# ACS723_Low_Current_Sensor_v01.net
KiCad netlist of a schematic drawn in EAGLE
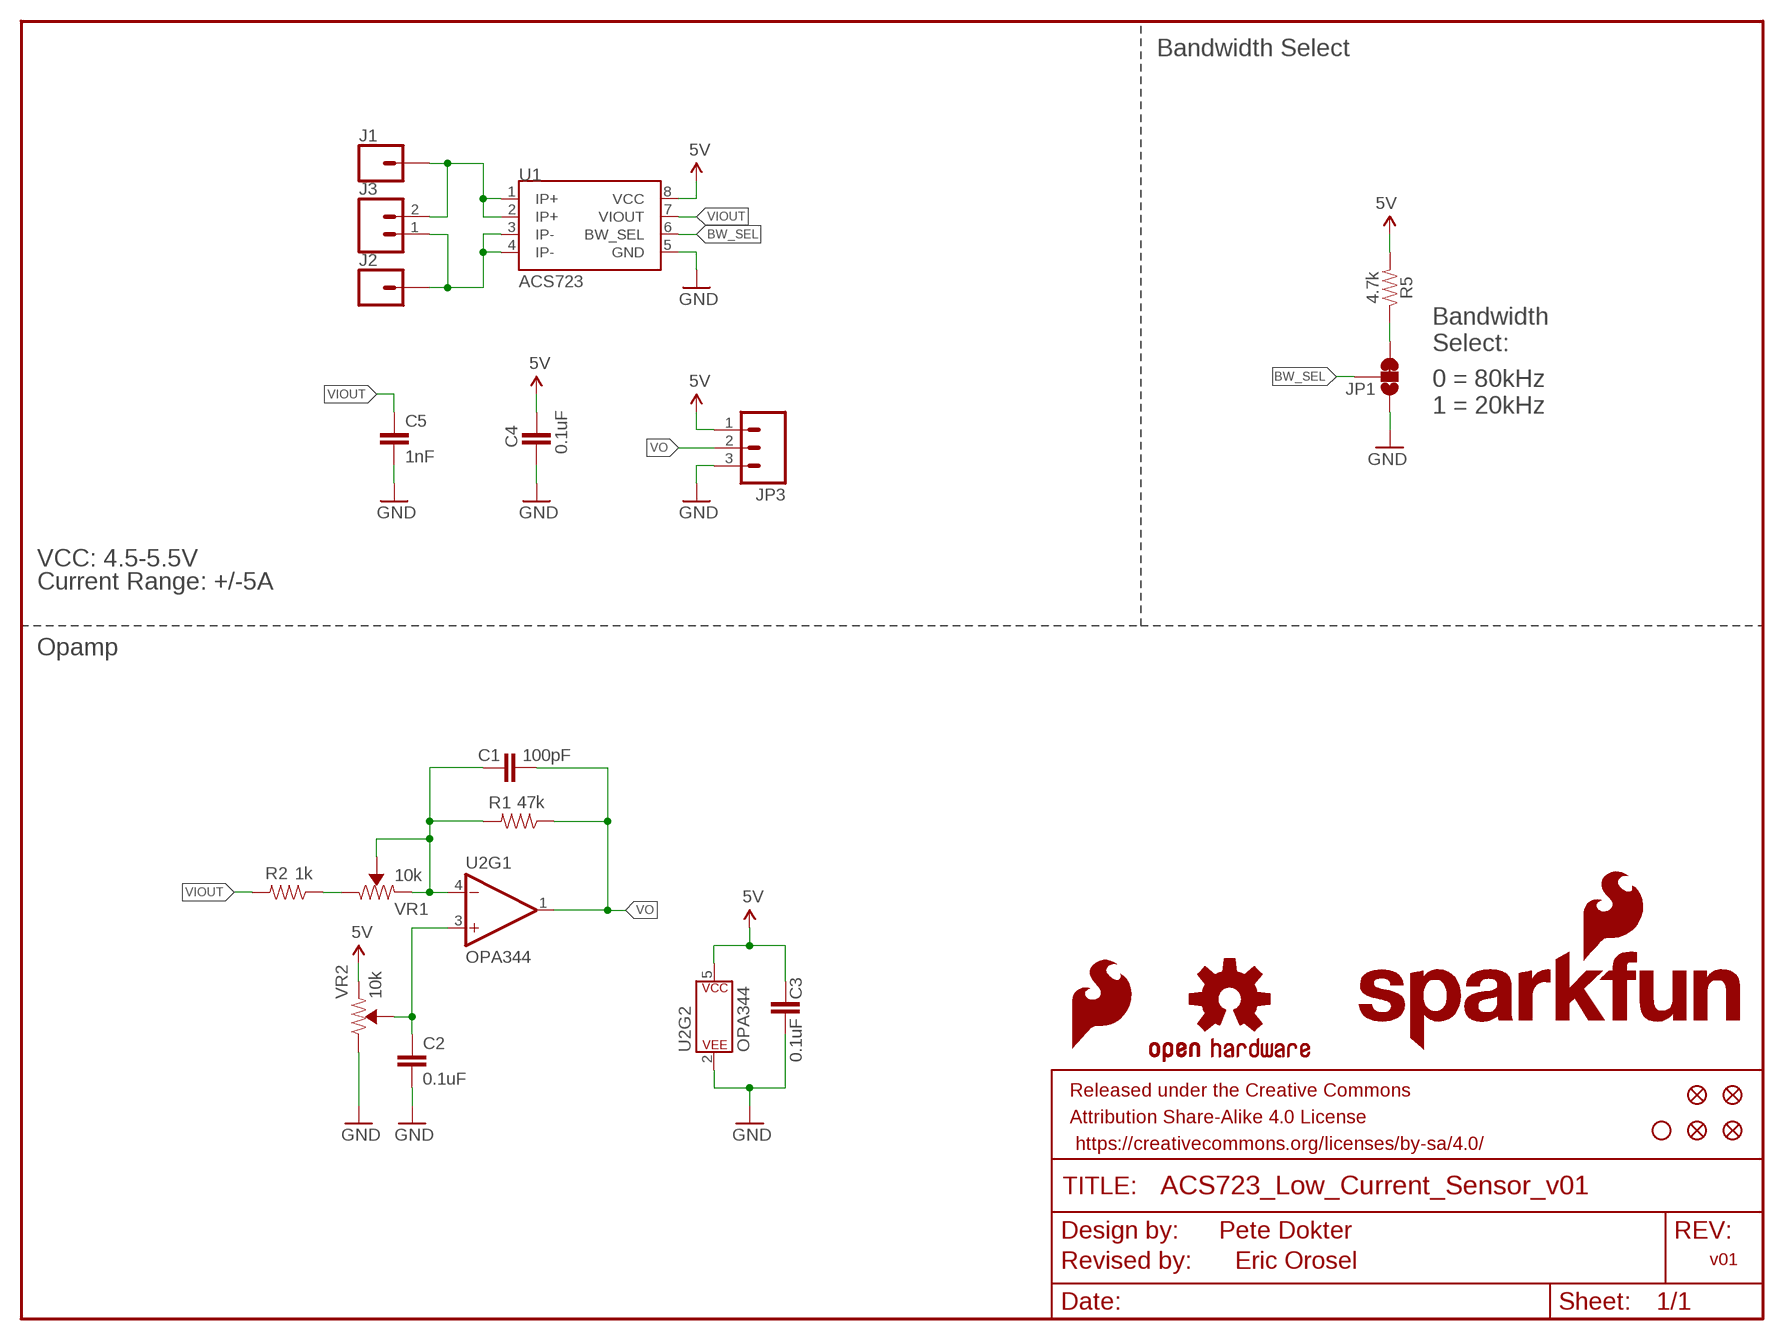
[diagram p0: schematic, sheet 1]

(export (version "E")
  (design (tool "Eeschema 10.0.6"))
  (components
    (comp (ref "C1")
      (value "100pF")
      (footprint "eagle-import:0603")
      (libsource (lib "eagle-import") (part "100PF-0603-50V-5%"))
    )
    (comp (ref "C2")
      (value "0.1uF")
      (footprint "eagle-import:0603")
      (libsource (lib "eagle-import") (part "0.1UF-0603-25V-(+80/-20%)"))
    )
    (comp (ref "C3")
      (value "0.1uF")
      (footprint "eagle-import:0603")
      (libsource (lib "eagle-import") (part "0.1UF-0603-25V-(+80/-20%)"))
    )
    (comp (ref "C4")
      (value "0.1uF")
      (footprint "eagle-import:0603")
      (libsource (lib "eagle-import") (part "0.1UF-0603-25V-(+80/-20%)"))
    )
    (comp (ref "C5")
      (value "1nF")
      (footprint "eagle-import:0603")
      (libsource (lib "eagle-import") (part "1.0NF/1000PF-0603-50V-10%"))
    )
    (comp (ref "FD1")
      (value "FIDUCIAL1X2")
      (footprint "eagle-import:FIDUCIAL-1X2")
      (libsource (lib "eagle-import") (part "FIDUCIAL1X2"))
    )
    (comp (ref "FD2")
      (value "FIDUCIAL1X2")
      (footprint "eagle-import:FIDUCIAL-1X2")
      (libsource (lib "eagle-import") (part "FIDUCIAL1X2"))
    )
    (comp (ref "FD3")
      (value "FIDUCIAL1X2")
      (footprint "eagle-import:FIDUCIAL-1X2")
      (libsource (lib "eagle-import") (part "FIDUCIAL1X2"))
    )
    (comp (ref "FD4")
      (value "FIDUCIAL1X2")
      (footprint "eagle-import:FIDUCIAL-1X2")
      (libsource (lib "eagle-import") (part "FIDUCIAL1X2"))
    )
    (comp (ref "FRAME1")
      (value "FRAME-LETTER")
      (footprint "eagle-import:CREATIVE_COMMONS")
      (libsource (lib "eagle-import") (part "FRAME-LETTER"))
    )
    (comp (ref "H1")
      (value "STAND-OFFTIGHT")
      (footprint "eagle-import:STAND-OFF-TIGHT")
      (libsource (lib "eagle-import") (part "STAND-OFFTIGHT"))
    )
    (comp (ref "J1")
      (value "CONN_01SMTSO-256-ET-0.165DIA")
      (footprint "eagle-import:SMTSO-256-ET-0.165DIA")
      (libsource (lib "eagle-import") (part "CONN_01SMTSO-256-ET-0.165DIA"))
    )
    (comp (ref "J2")
      (value "CONN_01SMTSO-256-ET-0.165DIA")
      (footprint "eagle-import:SMTSO-256-ET-0.165DIA")
      (libsource (lib "eagle-import") (part "CONN_01SMTSO-256-ET-0.165DIA"))
    )
    (comp (ref "J3")
      (value "CONN_021X02_NO_SILK")
      (footprint "eagle-import:1X02_NO_SILK")
      (libsource (lib "eagle-import") (part "CONN_021X02_NO_SILK"))
    )
    (comp (ref "JP1")
      (value "JUMPER-SMT_3_1-NC_TRACE_SILK")
      (footprint "eagle-import:SMT-JUMPER_3_1-NC_TRACE_SILK")
      (libsource (lib "eagle-import") (part "JUMPER-SMT_3_1-NC_TRACE_SILK"))
    )
    (comp (ref "JP3")
      (value "M03PTH")
      (footprint "eagle-import:1X03")
      (libsource (lib "eagle-import") (part "M03PTH"))
    )
    (comp (ref "LOGO1")
      (value "SFE_LOGO_NAME_FLAME.1_INCH")
      (footprint "eagle-import:SFE_LOGO_NAME_FLAME_.1")
      (libsource (lib "eagle-import") (part "SFE_LOGO_NAME_FLAME.1_INCH"))
    )
    (comp (ref "LOGO2")
      (value "OSHW-LOGOS")
      (footprint "eagle-import:OSHW-LOGO-S")
      (libsource (lib "eagle-import") (part "OSHW-LOGOS"))
    )
    (comp (ref "LOGO3")
      (value "SFE_LOGO_FLAME.1_INCH")
      (footprint "eagle-import:SFE_LOGO_FLAME_.1")
      (libsource (lib "eagle-import") (part "SFE_LOGO_FLAME.1_INCH"))
    )
    (comp (ref "R1")
      (value "47k")
      (footprint "eagle-import:0603")
      (libsource (lib "eagle-import") (part "47KOHM-0603-1/10W-1%"))
    )
    (comp (ref "R2")
      (value "1k")
      (footprint "eagle-import:0603")
      (libsource (lib "eagle-import") (part "1KOHM-0603-1/10W-1%"))
    )
    (comp (ref "R5")
      (value "4.7k")
      (footprint "eagle-import:0603")
      (libsource (lib "eagle-import") (part "4.7KOHM-0603-1/10W-1%"))
    )
    (comp (ref "U1")
      (value "ACS723")
      (footprint "eagle-import:SO08")
      (fields (field (name "PART_#") "ACS723ACS723LLCTR-05AB-T2"))
      (libsource (lib "eagle-import") (part "ACS723"))
    )
    (comp (ref "U2")
      (value "OPA344")
      (footprint "eagle-import:SOT23-5")
      (libsource (lib "eagle-import") (part "OPA344"))
    )
    (comp (ref "VR1")
      (value "10k")
      (footprint "eagle-import:TRIMPOT-SMD-TC33X")
      (libsource (lib "eagle-import") (part "TRIMPOT-SMD-3MM-OPEN-1/10W-25%"))
    )
    (comp (ref "VR2")
      (value "10k")
      (footprint "eagle-import:TRIMPOT-SMD-TC33X")
      (libsource (lib "eagle-import") (part "TRIMPOT-SMD-3MM-OPEN-1/10W-25%"))
    )
  )
  (nets
    (net (code "1") (name "5V") (class "Default")
      (node (ref "C3") (pin "1") (pinfunction "1_1") (pintype "passive"))
      (node (ref "C4") (pin "2") (pinfunction "2_2") (pintype "passive"))
      (node (ref "JP3") (pin "1") (pinfunction "1_1") (pintype "passive"))
      (node (ref "R5") (pin "2") (pinfunction "2_2") (pintype "passive"))
      (node (ref "U1") (pin "8") (pinfunction "VCC_8") (pintype "bidirectional"))
      (node (ref "U2") (pin "5") (pinfunction "P$V+_5") (pintype "bidirectional"))
      (node (ref "VR2") (pin "3") (pinfunction "CCW_3") (pintype "passive"))
    )
    (net (code "2") (name "BW_SEL") (class "Default")
      (node (ref "JP1") (pin "2") (pinfunction "2_2") (pintype "passive"))
      (node (ref "U1") (pin "6") (pinfunction "BW_SEL_6") (pintype "bidirectional"))
    )
    (net (code "3") (name "GND") (class "Default")
      (node (ref "C2") (pin "2") (pinfunction "2_2") (pintype "passive"))
      (node (ref "C3") (pin "2") (pinfunction "2_2") (pintype "passive"))
      (node (ref "C4") (pin "1") (pinfunction "1_1") (pintype "passive"))
      (node (ref "C5") (pin "2") (pinfunction "2_2") (pintype "passive"))
      (node (ref "JP1") (pin "1") (pinfunction "1_1") (pintype "passive"))
      (node (ref "JP3") (pin "3") (pinfunction "3_3") (pintype "passive"))
      (node (ref "U1") (pin "5") (pinfunction "GND_5") (pintype "bidirectional"))
      (node (ref "U2") (pin "2") (pinfunction "P$V-_2") (pintype "bidirectional"))
      (node (ref "VR2") (pin "1") (pinfunction "CW_1") (pintype "passive"))
    )
    (net (code "4") (name "Net-(J1-1)") (class "Default")
      (node (ref "J1") (pin "P$1") (pinfunction "1_P$1") (pintype "passive"))
      (node (ref "J3") (pin "2") (pinfunction "2_2") (pintype "passive"))
      (node (ref "U1") (pin "1") (pinfunction "IP+_1") (pintype "input"))
      (node (ref "U1") (pin "2") (pinfunction "IP+_2") (pintype "input"))
    )
    (net (code "5") (name "Net-(J2-1)") (class "Default")
      (node (ref "J2") (pin "P$1") (pinfunction "1_P$1") (pintype "passive"))
      (node (ref "J3") (pin "1") (pinfunction "1_1") (pintype "passive"))
      (node (ref "U1") (pin "3") (pinfunction "IP-_3") (pintype "bidirectional"))
      (node (ref "U1") (pin "4") (pinfunction "IP-_4") (pintype "bidirectional"))
    )
    (net (code "6") (name "Net-(JP1-Pad3)") (class "Default")
      (node (ref "JP1") (pin "3") (pinfunction "3_3") (pintype "passive"))
      (node (ref "R5") (pin "1") (pinfunction "1_1") (pintype "passive"))
    )
    (net (code "7") (name "Net-(U2A-+IN)") (class "Default")
      (node (ref "C2") (pin "1") (pinfunction "1_1") (pintype "passive"))
      (node (ref "U2") (pin "3") (pinfunction "+IN_3") (pintype "input"))
      (node (ref "VR2") (pin "2") (pinfunction "WIPER_2") (pintype "passive"))
    )
    (net (code "8") (name "Net-(U2A--IN)") (class "Default")
      (node (ref "C1") (pin "2") (pinfunction "2_2") (pintype "passive"))
      (node (ref "R1") (pin "2") (pinfunction "2_2") (pintype "passive"))
      (node (ref "U2") (pin "4") (pinfunction "-IN_4") (pintype "input"))
      (node (ref "VR1") (pin "2") (pinfunction "WIPER_2") (pintype "passive"))
      (node (ref "VR1") (pin "3") (pinfunction "CCW_3") (pintype "passive"))
    )
    (net (code "9") (name "Net-(VR1-CW)") (class "Default")
      (node (ref "R2") (pin "1") (pinfunction "1_1") (pintype "passive"))
      (node (ref "VR1") (pin "1") (pinfunction "CW_1") (pintype "passive"))
    )
    (net (code "10") (name "VIOUT") (class "Default")
      (node (ref "C5") (pin "1") (pinfunction "1_1") (pintype "passive"))
      (node (ref "R2") (pin "2") (pinfunction "2_2") (pintype "passive"))
      (node (ref "U1") (pin "7") (pinfunction "VIOUT_7") (pintype "bidirectional"))
    )
    (net (code "11") (name "VO") (class "Default")
      (node (ref "C1") (pin "1") (pinfunction "1_1") (pintype "passive"))
      (node (ref "JP3") (pin "2") (pinfunction "2_2") (pintype "passive"))
      (node (ref "R1") (pin "1") (pinfunction "1_1") (pintype "passive"))
      (node (ref "U2") (pin "1") (pinfunction "OUT_1") (pintype "output"))
    )
  )
)
